# ZYNQ-JTAG.net
KiCad netlist of a schematic drawn in Altium Designer
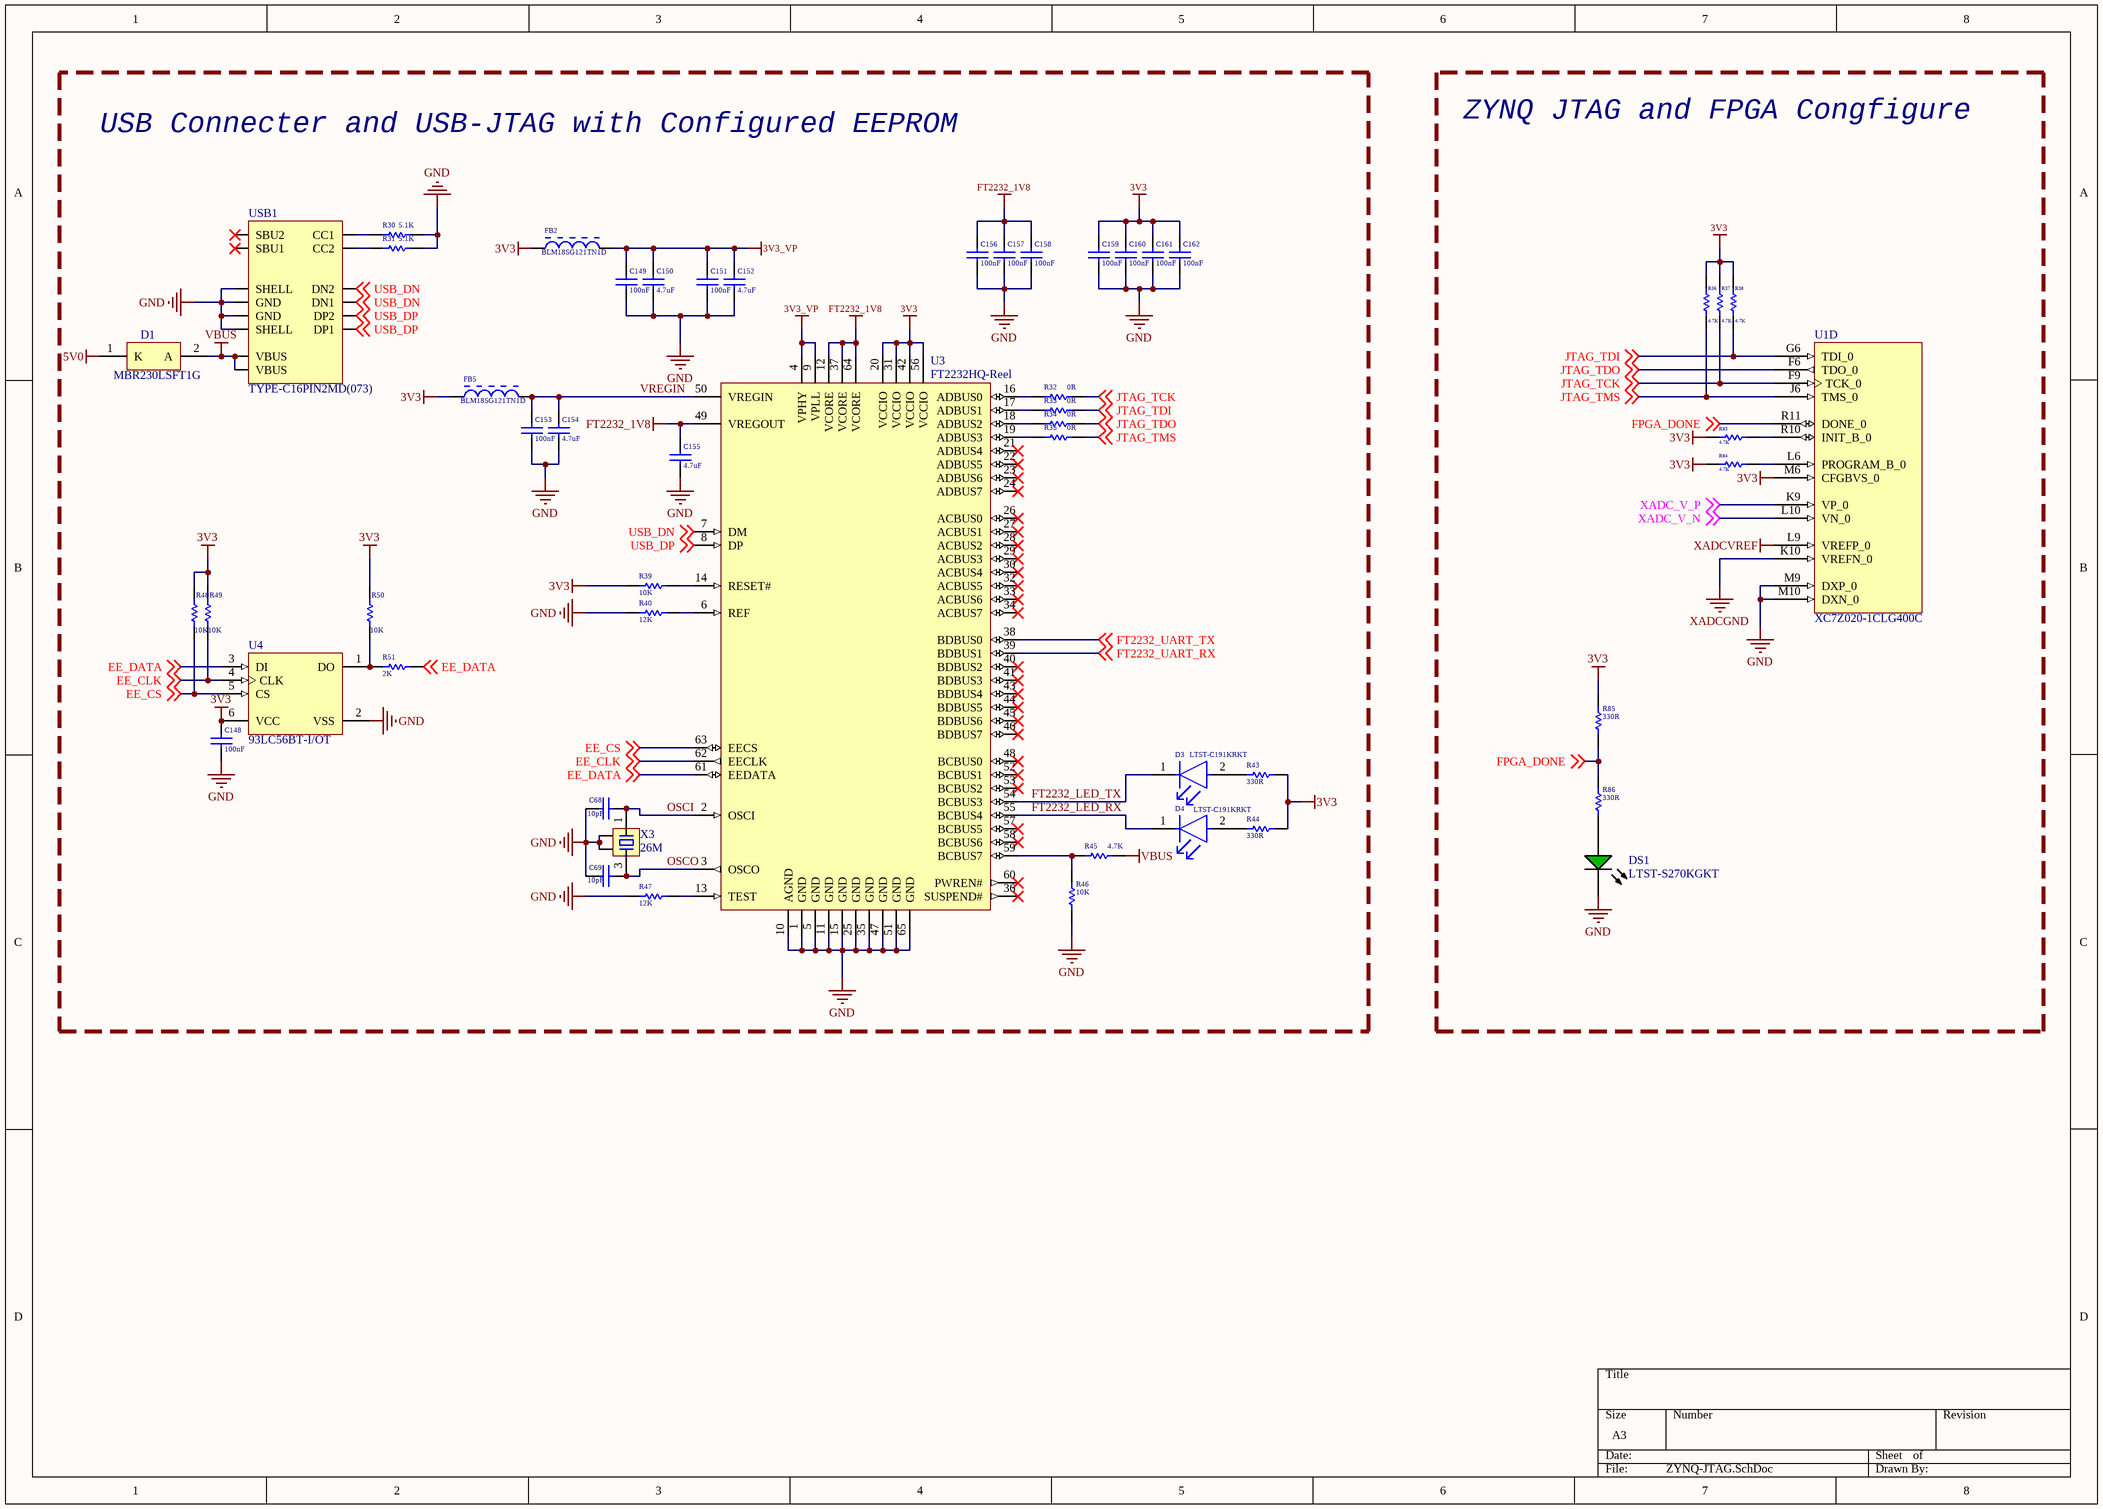
[diagram p0: ZYNQ-JTAG.SchDoc]

(export (version "E")
  (design (tool "Eeschema 10.0.6"))
  (components
    (comp (ref "C68")
      (value "10pF")
      (footprint "CAPC1005X55X25LL05T10")
      (fields (field (name "PART NUMBER") "GRM155R71H104KE14D") (field (name "MANUFACTURER") "Murata"))
      (libsource (lib "Altium Content Vault") (part "CAP"))
    )
    (comp (ref "C69")
      (value "10pF")
      (footprint "CAPC1005X55X25LL05T10")
      (fields (field (name "PART NUMBER") "GRM155R71H104KE14D") (field (name "MANUFACTURER") "Murata"))
      (libsource (lib "Altium Content Vault") (part "CAP"))
    )
    (comp (ref "C148")
      (value "100nF")
      (footprint "CAPC1005X55X25LL05T10")
      (fields (field (name "PART NUMBER") "GRM155R71H104KE14D") (field (name "MANUFACTURER") "Murata"))
      (libsource (lib "Altium Content Vault") (part "CAP"))
    )
    (comp (ref "C149")
      (value "100nF")
      (footprint "CAPC1005X55X25LL05T10")
      (fields (field (name "PART NUMBER") "GRM155R71H104KE14D") (field (name "MANUFACTURER") "Murata"))
      (libsource (lib "Altium Content Vault") (part "CAP"))
    )
    (comp (ref "C150")
      (value "4.7uF")
      (footprint "CAPC1005X55X25LL05T10")
      (fields (field (name "PART NUMBER") "GRM155R71H104KE14D") (field (name "MANUFACTURER") "Murata"))
      (libsource (lib "Altium Content Vault") (part "CAP"))
    )
    (comp (ref "C151")
      (value "100nF")
      (footprint "CAPC1005X55X25LL05T10")
      (fields (field (name "PART NUMBER") "GRM155R71H104KE14D") (field (name "MANUFACTURER") "Murata"))
      (libsource (lib "Altium Content Vault") (part "CAP"))
    )
    (comp (ref "C152")
      (value "4.7uF")
      (footprint "CAPC1005X55X25LL05T10")
      (fields (field (name "PART NUMBER") "GRM155R71H104KE14D") (field (name "MANUFACTURER") "Murata"))
      (libsource (lib "Altium Content Vault") (part "CAP"))
    )
    (comp (ref "C153")
      (value "100nF")
      (footprint "CAPC1005X55X25LL05T10")
      (fields (field (name "PART NUMBER") "GRM155R71H104KE14D") (field (name "MANUFACTURER") "Murata"))
      (libsource (lib "Altium Content Vault") (part "CAP"))
    )
    (comp (ref "C154")
      (value "4.7uF")
      (footprint "CAPC1005X55X25LL05T10")
      (fields (field (name "PART NUMBER") "GRM155R71H104KE14D") (field (name "MANUFACTURER") "Murata"))
      (libsource (lib "Altium Content Vault") (part "CAP"))
    )
    (comp (ref "C155")
      (value "4.7uF")
      (footprint "CAPC1005X55X25LL05T10")
      (fields (field (name "PART NUMBER") "GRM155R71H104KE14D") (field (name "MANUFACTURER") "Murata"))
      (libsource (lib "Altium Content Vault") (part "CAP"))
    )
    (comp (ref "C156")
      (value "100nF")
      (footprint "CAPC1005X55X25LL05T10")
      (fields (field (name "PART NUMBER") "GRM155R71H104KE14D") (field (name "MANUFACTURER") "Murata"))
      (libsource (lib "Altium Content Vault") (part "CAP"))
    )
    (comp (ref "C157")
      (value "100nF")
      (footprint "CAPC1005X55X25LL05T10")
      (fields (field (name "PART NUMBER") "GRM155R71H104KE14D") (field (name "MANUFACTURER") "Murata"))
      (libsource (lib "Altium Content Vault") (part "CAP"))
    )
    (comp (ref "C158")
      (value "100nF")
      (footprint "CAPC1005X55X25LL05T10")
      (fields (field (name "PART NUMBER") "GRM155R71H104KE14D") (field (name "MANUFACTURER") "Murata"))
      (libsource (lib "Altium Content Vault") (part "CAP"))
    )
    (comp (ref "C159")
      (value "100nF")
      (footprint "CAPC1005X55X25LL05T10")
      (fields (field (name "PART NUMBER") "GRM155R71H104KE14D") (field (name "MANUFACTURER") "Murata"))
      (libsource (lib "Altium Content Vault") (part "CAP"))
    )
    (comp (ref "C160")
      (value "100nF")
      (footprint "CAPC1005X55X25LL05T10")
      (fields (field (name "PART NUMBER") "GRM155R71H104KE14D") (field (name "MANUFACTURER") "Murata"))
      (libsource (lib "Altium Content Vault") (part "CAP"))
    )
    (comp (ref "C161")
      (value "100nF")
      (footprint "CAPC1005X55X25LL05T10")
      (fields (field (name "PART NUMBER") "GRM155R71H104KE14D") (field (name "MANUFACTURER") "Murata"))
      (libsource (lib "Altium Content Vault") (part "CAP"))
    )
    (comp (ref "C162")
      (value "100nF")
      (footprint "CAPC1005X55X25LL05T10")
      (fields (field (name "PART NUMBER") "GRM155R71H104KE14D") (field (name "MANUFACTURER") "Murata"))
      (libsource (lib "Altium Content Vault") (part "CAP"))
    )
    (comp (ref "D1")
      (value "MBR230LSFT1G")
      (footprint "ONSC-SOD-123FL-2-498-01_V")
      (description "Schottky Power Rectifier, 2-Pin SOD-123, Pb-Free, Tape and Reel")
      (fields (field (name "MANUFACTURER") "On Semiconductor"))
      (libsource (lib "Altium Content Vault") (part "ONSC-D-K1A2-2_A"))
    )
    (comp (ref "D3")
      (value "LTST-C191KRKT")
      (footprint "FP-LTST-C191KRKT-MFG")
      (libsource (lib "Altium Content Vault") (part "8706943c75ba83719d021d2fdc84c58"))
    )
    (comp (ref "D4")
      (value "LTST-C191KRKT")
      (footprint "FP-LTST-C191KRKT-MFG")
      (libsource (lib "Altium Content Vault") (part "8706943c75ba83719d021d2fdc84c58"))
    )
    (comp (ref "DS1")
      (value "LTST-S270KGKT")
      (footprint "LTST-LTST-S270KGKT-2_V")
      (description "Ultra Bright AlInGaP Chip LED, 75 mW, -30 to 85 degC, 2-Pin SMD (0604), RoHS, Tape and Reel")
      (fields (field (name "MANUFACTURER") "Lite-On"))
      (libsource (lib "Altium Content Vault") (part "LED-GREEN-KA-2"))
    )
    (comp (ref "FB2")
      (value "BLM18SG121TN1D")
      (footprint "MURA-BLM18SG-B40-CHIP-2_V6")
      (fields (field (name "MANUFACTURER") "Murata"))
      (libsource (lib "Altium Content Vault") (part "MURA-FB-2"))
    )
    (comp (ref "FB5")
      (value "BLM18SG121TN1D")
      (footprint "MURA-BLM18SG-B40-CHIP-2_V6")
      (fields (field (name "MANUFACTURER") "Murata"))
      (libsource (lib "Altium Content Vault") (part "MURA-FB-2"))
    )
    (comp (ref "R30")
      (value "5.1K")
      (footprint "RESC1005X40X25LL05T05")
      (fields (field (name "MANUFACTURER") "Panasonic") (field (name "PART NUMBER") "ERJ-2RKF40R2X"))
      (libsource (lib "Altium Content Vault") (part "RES"))
    )
    (comp (ref "R31")
      (value "5.1K")
      (footprint "RESC1005X40X25LL05T05")
      (fields (field (name "MANUFACTURER") "Panasonic") (field (name "PART NUMBER") "ERJ-2RKF40R2X"))
      (libsource (lib "Altium Content Vault") (part "RES"))
    )
    (comp (ref "R32")
      (value "0R")
      (footprint "RESC1005X40X25LL05T05")
      (fields (field (name "MANUFACTURER") "Panasonic") (field (name "PART NUMBER") "ERJ-2RKF40R2X"))
      (libsource (lib "Altium Content Vault") (part "RES"))
    )
    (comp (ref "R33")
      (value "0R")
      (footprint "RESC1005X40X25LL05T05")
      (fields (field (name "MANUFACTURER") "Panasonic") (field (name "PART NUMBER") "ERJ-2RKF40R2X"))
      (libsource (lib "Altium Content Vault") (part "RES"))
    )
    (comp (ref "R34")
      (value "0R")
      (footprint "RESC1005X40X25LL05T05")
      (fields (field (name "MANUFACTURER") "Panasonic") (field (name "PART NUMBER") "ERJ-2RKF40R2X"))
      (libsource (lib "Altium Content Vault") (part "RES"))
    )
    (comp (ref "R35")
      (value "0R")
      (footprint "RESC1005X40X25LL05T05")
      (fields (field (name "MANUFACTURER") "Panasonic") (field (name "PART NUMBER") "ERJ-2RKF40R2X"))
      (libsource (lib "Altium Content Vault") (part "RES"))
    )
    (comp (ref "R36")
      (value "4.7K")
      (footprint "RESC1005X40X25LL05T05")
      (fields (field (name "MANUFACTURER") "Panasonic") (field (name "PART NUMBER") "ERJ-2RKF40R2X"))
      (libsource (lib "Altium Content Vault") (part "RES"))
    )
    (comp (ref "R37")
      (value "4.7K")
      (footprint "RESC1005X40X25LL05T05")
      (fields (field (name "MANUFACTURER") "Panasonic") (field (name "PART NUMBER") "ERJ-2RKF40R2X"))
      (libsource (lib "Altium Content Vault") (part "RES"))
    )
    (comp (ref "R38")
      (value "4.7K")
      (footprint "RESC1005X40X25LL05T05")
      (fields (field (name "MANUFACTURER") "Panasonic") (field (name "PART NUMBER") "ERJ-2RKF40R2X"))
      (libsource (lib "Altium Content Vault") (part "RES"))
    )
    (comp (ref "R39")
      (value "10K")
      (footprint "RESC1005X40X25LL05T05")
      (fields (field (name "MANUFACTURER") "Panasonic") (field (name "PART NUMBER") "ERJ-2RKF40R2X"))
      (libsource (lib "Altium Content Vault") (part "RES"))
    )
    (comp (ref "R40")
      (value "12K")
      (footprint "RESC1005X40X25LL05T05")
      (fields (field (name "MANUFACTURER") "Panasonic") (field (name "PART NUMBER") "ERJ-2RKF40R2X"))
      (libsource (lib "Altium Content Vault") (part "RES"))
    )
    (comp (ref "R43")
      (value "330R")
      (footprint "RESC1005X40X25LL05T05")
      (fields (field (name "MANUFACTURER") "Panasonic") (field (name "PART NUMBER") "ERJ-2RKF40R2X"))
      (libsource (lib "Altium Content Vault") (part "RES"))
    )
    (comp (ref "R44")
      (value "330R")
      (footprint "RESC1005X40X25LL05T05")
      (fields (field (name "MANUFACTURER") "Panasonic") (field (name "PART NUMBER") "ERJ-2RKF40R2X"))
      (libsource (lib "Altium Content Vault") (part "RES"))
    )
    (comp (ref "R45")
      (value "4.7K")
      (footprint "RESC1005X40X25LL05T05")
      (fields (field (name "MANUFACTURER") "Panasonic") (field (name "PART NUMBER") "ERJ-2RKF40R2X"))
      (libsource (lib "Altium Content Vault") (part "RES"))
    )
    (comp (ref "R46")
      (value "10K")
      (footprint "RESC1005X40X25LL05T05")
      (fields (field (name "MANUFACTURER") "Panasonic") (field (name "PART NUMBER") "ERJ-2RKF40R2X"))
      (libsource (lib "Altium Content Vault") (part "RES"))
    )
    (comp (ref "R47")
      (value "12K")
      (footprint "RESC1005X40X25LL05T05")
      (fields (field (name "MANUFACTURER") "Panasonic") (field (name "PART NUMBER") "ERJ-2RKF40R2X"))
      (libsource (lib "Altium Content Vault") (part "RES"))
    )
    (comp (ref "R48")
      (value "10K")
      (footprint "RESC1005X40X25LL05T05")
      (fields (field (name "MANUFACTURER") "Panasonic") (field (name "PART NUMBER") "ERJ-2RKF40R2X"))
      (libsource (lib "Altium Content Vault") (part "RES"))
    )
    (comp (ref "R49")
      (value "10K")
      (footprint "RESC1005X40X25LL05T05")
      (fields (field (name "MANUFACTURER") "Panasonic") (field (name "PART NUMBER") "ERJ-2RKF40R2X"))
      (libsource (lib "Altium Content Vault") (part "RES"))
    )
    (comp (ref "R50")
      (value "10K")
      (footprint "RESC1005X40X25LL05T05")
      (fields (field (name "MANUFACTURER") "Panasonic") (field (name "PART NUMBER") "ERJ-2RKF40R2X"))
      (libsource (lib "Altium Content Vault") (part "RES"))
    )
    (comp (ref "R51")
      (value "2K")
      (footprint "RESC1005X40X25LL05T05")
      (fields (field (name "MANUFACTURER") "Panasonic") (field (name "PART NUMBER") "ERJ-2RKF40R2X"))
      (libsource (lib "Altium Content Vault") (part "RES"))
    )
    (comp (ref "R83")
      (value "4.7K")
      (footprint "RESC1005X40X25LL05T05")
      (fields (field (name "MANUFACTURER") "Panasonic") (field (name "PART NUMBER") "ERJ-2RKF40R2X"))
      (libsource (lib "Altium Content Vault") (part "RES"))
    )
    (comp (ref "R84")
      (value "4.7K")
      (footprint "RESC1005X40X25LL05T05")
      (fields (field (name "MANUFACTURER") "Panasonic") (field (name "PART NUMBER") "ERJ-2RKF40R2X"))
      (libsource (lib "Altium Content Vault") (part "RES"))
    )
    (comp (ref "R85")
      (value "330R")
      (footprint "RESC1005X40X25LL05T05")
      (fields (field (name "MANUFACTURER") "Panasonic") (field (name "PART NUMBER") "ERJ-2RKF40R2X"))
      (libsource (lib "Altium Content Vault") (part "RES"))
    )
    (comp (ref "R86")
      (value "330R")
      (footprint "RESC1005X40X25LL05T05")
      (fields (field (name "MANUFACTURER") "Panasonic") (field (name "PART NUMBER") "ERJ-2RKF40R2X"))
      (libsource (lib "Altium Content Vault") (part "RES"))
    )
    (comp (ref "U1")
      (value "XC7Z020-1CLG400C")
      (footprint "CLG400")
      (fields (field (name "GENERIC PART NUMBER") "XC7Z020"))
      (libsource (lib "Altium Content Vault") (part "XNLX-XC7Z020-CLG400"))
    )
    (comp (ref "U3")
      (value "FT2232HQ-Reel")
      (footprint "QFN64_2_L")
      (description "Dual High Speed USB To Multipurpose UART/FIFO IC, 64-pin QFN, Tape and Reel")
      (fields (field (name "MANUFACTURER") "FTDI"))
      (libsource (lib "Altium Content Vault") (part "COM-UART-FT2232H-QFN64"))
    )
    (comp (ref "U4")
      (value "93LC56BT-I/OT")
      (footprint "SOT-23-OT6_N")
      (description "2K, 128x16-bit, 2.5V Microwire Serial EEPROM, 6-Pin SOT-23, Industrial Temperature, Tape and Reel")
      (libsource (lib "Altium Content Vault") (part "MEM-SEEPROM-93AA46B-OT-6"))
    )
    (comp (ref "USB1")
      (value "TYPE-C16PIN2MD(073)")
      (footprint "TYPE-C16PIN2MD(073)-Footprint")
      (description "Type-C 母 卧贴 带定位柱 不锈钢外壳 2次模顶")
      (libsource (lib "HainanU-RoboMaster-硬件组") (part "TypeC-16P"))
    )
    (comp (ref "X3")
      (value "26M")
      (footprint "XTAL-3225-4P")
      (description "4脚无源晶振(谐振器）")
      (libsource (lib "0.1 - 电阻-电容-电感-保险丝-晶振-晶体-磁珠-电位器-法拉电容-馈通电容") (part "XTAL-4P"))
    )
  )
  (nets
    (net (code "1") (name "/FT2232_LED_RX") (class "Default")
      (node (ref "D4") (pin "1") (pinfunction "C_1") (pintype "passive"))
      (node (ref "U3") (pin "55") (pinfunction "BCBUS4_55") (pintype "bidirectional"))
    )
    (net (code "2") (name "/FT2232_LED_TX") (class "Default")
      (node (ref "D3") (pin "1") (pinfunction "C_1") (pintype "passive"))
      (node (ref "U3") (pin "54") (pinfunction "BCBUS3_54") (pintype "bidirectional"))
    )
    (net (code "3") (name "/OSCI") (class "Default")
      (node (ref "C68") (pin "1") (pinfunction "1_1") (pintype "passive"))
      (node (ref "U3") (pin "2") (pinfunction "OSCI_2") (pintype "input"))
      (node (ref "X3") (pin "1") (pinfunction "1_1") (pintype "passive"))
    )
    (net (code "4") (name "/OSCO") (class "Default")
      (node (ref "C69") (pin "1") (pinfunction "1_1") (pintype "passive"))
      (node (ref "U3") (pin "3") (pinfunction "OSCO_3") (pintype "output"))
      (node (ref "X3") (pin "3") (pinfunction "3_3") (pintype "passive"))
    )
    (net (code "5") (name "/VREGIN") (class "Default")
      (node (ref "C153") (pin "1") (pinfunction "1_1") (pintype "passive"))
      (node (ref "C154") (pin "1") (pinfunction "1_1") (pintype "passive"))
      (node (ref "FB5") (pin "2") (pinfunction "2_2") (pintype "passive"))
      (node (ref "U3") (pin "50") (pinfunction "VREGIN_50") (pintype "power_in"))
    )
    (net (code "6") (name "3V3") (class "Default")
      (node (ref "C148") (pin "1") (pinfunction "1_1") (pintype "passive"))
      (node (ref "C159") (pin "1") (pinfunction "1_1") (pintype "passive"))
      (node (ref "C160") (pin "1") (pinfunction "1_1") (pintype "passive"))
      (node (ref "C161") (pin "1") (pinfunction "1_1") (pintype "passive"))
      (node (ref "C162") (pin "1") (pinfunction "1_1") (pintype "passive"))
      (node (ref "FB2") (pin "1") (pinfunction "1_1") (pintype "passive"))
      (node (ref "FB5") (pin "1") (pinfunction "1_1") (pintype "passive"))
      (node (ref "R36") (pin "1") (pinfunction "1_1") (pintype "passive"))
      (node (ref "R37") (pin "1") (pinfunction "1_1") (pintype "passive"))
      (node (ref "R38") (pin "1") (pinfunction "1_1") (pintype "passive"))
      (node (ref "R39") (pin "2") (pinfunction "2_2") (pintype "passive"))
      (node (ref "R43") (pin "1") (pinfunction "1_1") (pintype "passive"))
      (node (ref "R44") (pin "1") (pinfunction "1_1") (pintype "passive"))
      (node (ref "R48") (pin "2") (pinfunction "2_2") (pintype "passive"))
      (node (ref "R49") (pin "2") (pinfunction "2_2") (pintype "passive"))
      (node (ref "R50") (pin "2") (pinfunction "2_2") (pintype "passive"))
      (node (ref "R83") (pin "1") (pinfunction "1_1") (pintype "passive"))
      (node (ref "R84") (pin "1") (pinfunction "1_1") (pintype "passive"))
      (node (ref "R85") (pin "2") (pinfunction "2_2") (pintype "passive"))
      (node (ref "U1") (pin "M6") (pinfunction "CFGBVS_0_M6") (pintype "input"))
      (node (ref "U3") (pin "20") (pinfunction "VCCIO_20") (pintype "power_in"))
      (node (ref "U3") (pin "31") (pinfunction "VCCIO_31") (pintype "power_in"))
      (node (ref "U3") (pin "42") (pinfunction "VCCIO_42") (pintype "power_in"))
      (node (ref "U3") (pin "56") (pinfunction "VCCIO_56") (pintype "power_in"))
      (node (ref "U4") (pin "6") (pinfunction "VCC_6") (pintype "power_in"))
    )
    (net (code "7") (name "3V3_VP") (class "Default")
      (node (ref "C149") (pin "1") (pinfunction "1_1") (pintype "passive"))
      (node (ref "C150") (pin "1") (pinfunction "1_1") (pintype "passive"))
      (node (ref "C151") (pin "1") (pinfunction "1_1") (pintype "passive"))
      (node (ref "C152") (pin "1") (pinfunction "1_1") (pintype "passive"))
      (node (ref "FB2") (pin "2") (pinfunction "2_2") (pintype "passive"))
      (node (ref "U3") (pin "4") (pinfunction "VPHY_4") (pintype "power_in"))
      (node (ref "U3") (pin "9") (pinfunction "VPLL_9") (pintype "power_in"))
    )
    (net (code "8") (name "5V0") (class "Default")
      (node (ref "D1") (pin "1") (pinfunction "K_1") (pintype "passive"))
    )
    (net (code "9") (name "EE_CLK") (class "Default")
      (node (ref "R49") (pin "1") (pinfunction "1_1") (pintype "passive"))
      (node (ref "U3") (pin "62") (pinfunction "EECLK_62") (pintype "output"))
      (node (ref "U4") (pin "4") (pinfunction "CLK_4") (pintype "input"))
    )
    (net (code "10") (name "EE_CS") (class "Default")
      (node (ref "R48") (pin "1") (pinfunction "1_1") (pintype "passive"))
      (node (ref "U3") (pin "63") (pinfunction "EECS_63") (pintype "bidirectional"))
      (node (ref "U4") (pin "5") (pinfunction "CS_5") (pintype "input"))
    )
    (net (code "11") (name "EE_DATA") (class "Default")
      (node (ref "R51") (pin "1") (pinfunction "1_1") (pintype "passive"))
      (node (ref "U3") (pin "61") (pinfunction "EEDATA_61") (pintype "bidirectional"))
      (node (ref "U4") (pin "3") (pinfunction "DI_3") (pintype "input"))
    )
    (net (code "12") (name "FPGA_DONE") (class "Default")
      (node (ref "R85") (pin "1") (pinfunction "1_1") (pintype "passive"))
      (node (ref "R86") (pin "2") (pinfunction "2_2") (pintype "passive"))
      (node (ref "U1") (pin "R11") (pinfunction "DONE_0_R11") (pintype "bidirectional"))
    )
    (net (code "13") (name "FT2232_1V8") (class "Default")
      (node (ref "C155") (pin "1") (pinfunction "1_1") (pintype "passive"))
      (node (ref "C156") (pin "1") (pinfunction "1_1") (pintype "passive"))
      (node (ref "C157") (pin "1") (pinfunction "1_1") (pintype "passive"))
      (node (ref "C158") (pin "1") (pinfunction "1_1") (pintype "passive"))
      (node (ref "U3") (pin "12") (pinfunction "VCORE_12") (pintype "power_in"))
      (node (ref "U3") (pin "37") (pinfunction "VCORE_37") (pintype "power_in"))
      (node (ref "U3") (pin "49") (pinfunction "VREGOUT_49") (pintype "power_in"))
      (node (ref "U3") (pin "64") (pinfunction "VCORE_64") (pintype "power_in"))
    )
    (net (code "14") (name "FT2232_UART_RX") (class "Default")
      (node (ref "U3") (pin "39") (pinfunction "BDBUS1_39") (pintype "bidirectional"))
    )
    (net (code "15") (name "FT2232_UART_TX") (class "Default")
      (node (ref "U3") (pin "38") (pinfunction "BDBUS0_38") (pintype "bidirectional"))
    )
    (net (code "16") (name "GND") (class "Default")
      (node (ref "C148") (pin "2") (pinfunction "2_2") (pintype "passive"))
      (node (ref "C149") (pin "2") (pinfunction "2_2") (pintype "passive"))
      (node (ref "C150") (pin "2") (pinfunction "2_2") (pintype "passive"))
      (node (ref "C151") (pin "2") (pinfunction "2_2") (pintype "passive"))
      (node (ref "C152") (pin "2") (pinfunction "2_2") (pintype "passive"))
      (node (ref "C153") (pin "2") (pinfunction "2_2") (pintype "passive"))
      (node (ref "C154") (pin "2") (pinfunction "2_2") (pintype "passive"))
      (node (ref "C155") (pin "2") (pinfunction "2_2") (pintype "passive"))
      (node (ref "C156") (pin "2") (pinfunction "2_2") (pintype "passive"))
      (node (ref "C157") (pin "2") (pinfunction "2_2") (pintype "passive"))
      (node (ref "C158") (pin "2") (pinfunction "2_2") (pintype "passive"))
      (node (ref "C159") (pin "2") (pinfunction "2_2") (pintype "passive"))
      (node (ref "C160") (pin "2") (pinfunction "2_2") (pintype "passive"))
      (node (ref "C161") (pin "2") (pinfunction "2_2") (pintype "passive"))
      (node (ref "C162") (pin "2") (pinfunction "2_2") (pintype "passive"))
      (node (ref "C68") (pin "2") (pinfunction "2_2") (pintype "passive"))
      (node (ref "C69") (pin "2") (pinfunction "2_2") (pintype "passive"))
      (node (ref "DS1") (pin "1") (pinfunction "K_1") (pintype "passive"))
      (node (ref "R30") (pin "1") (pinfunction "1_1") (pintype "passive"))
      (node (ref "R31") (pin "1") (pinfunction "1_1") (pintype "passive"))
      (node (ref "R40") (pin "1") (pinfunction "1_1") (pintype "passive"))
      (node (ref "R46") (pin "1") (pinfunction "1_1") (pintype "passive"))
      (node (ref "R47") (pin "1") (pinfunction "1_1") (pintype "passive"))
      (node (ref "U1") (pin "M10") (pinfunction "DXN_0_M10") (pintype "input"))
      (node (ref "U1") (pin "M9") (pinfunction "DXP_0_M9") (pintype "input"))
      (node (ref "U3") (pin "1") (pinfunction "GND_1") (pintype "power_in"))
      (node (ref "U3") (pin "10") (pinfunction "AGND_10") (pintype "power_in"))
      (node (ref "U3") (pin "11") (pinfunction "GND_11") (pintype "power_in"))
      (node (ref "U3") (pin "15") (pinfunction "GND_15") (pintype "power_in"))
      (node (ref "U3") (pin "25") (pinfunction "GND_25") (pintype "power_in"))
      (node (ref "U3") (pin "35") (pinfunction "GND_35") (pintype "power_in"))
      (node (ref "U3") (pin "47") (pinfunction "GND_47") (pintype "power_in"))
      (node (ref "U3") (pin "5") (pinfunction "GND_5") (pintype "power_in"))
      (node (ref "U3") (pin "51") (pinfunction "GND_51") (pintype "power_in"))
      (node (ref "U3") (pin "65") (pinfunction "GND_65") (pintype "power_in"))
      (node (ref "U4") (pin "2") (pinfunction "VSS_2") (pintype "power_in"))
      (node (ref "USB1") (pin "1") (pinfunction "GND_1") (pintype "passive"))
      (node (ref "USB1") (pin "12") (pinfunction "GND_12") (pintype "passive"))
      (node (ref "USB1") (pin "13") (pinfunction "SHELL_13") (pintype "passive"))
      (node (ref "USB1") (pin "14") (pinfunction "SHELL_14") (pintype "passive"))
      (node (ref "X3") (pin "2") (pinfunction "2_2") (pintype "passive"))
      (node (ref "X3") (pin "4") (pinfunction "4_4") (pintype "passive"))
    )
    (net (code "17") (name "JTAG_TCK") (class "Default")
      (node (ref "R32") (pin "2") (pinfunction "2_2") (pintype "passive"))
      (node (ref "R37") (pin "2") (pinfunction "2_2") (pintype "passive"))
      (node (ref "U1") (pin "F9") (pinfunction "TCK_0_F9") (pintype "input"))
    )
    (net (code "18") (name "JTAG_TDI") (class "Default")
      (node (ref "R33") (pin "2") (pinfunction "2_2") (pintype "passive"))
      (node (ref "R38") (pin "2") (pinfunction "2_2") (pintype "passive"))
      (node (ref "U1") (pin "G6") (pinfunction "TDI_0_G6") (pintype "input"))
    )
    (net (code "19") (name "JTAG_TDO") (class "Default")
      (node (ref "R34") (pin "2") (pinfunction "2_2") (pintype "passive"))
      (node (ref "U1") (pin "F6") (pinfunction "TDO_0_F6") (pintype "output"))
    )
    (net (code "20") (name "JTAG_TMS") (class "Default")
      (node (ref "R35") (pin "2") (pinfunction "2_2") (pintype "passive"))
      (node (ref "R36") (pin "2") (pinfunction "2_2") (pintype "passive"))
      (node (ref "U1") (pin "J6") (pinfunction "TMS_0_J6") (pintype "input"))
    )
    (net (code "21") (name "Net-(D3-A)") (class "Default")
      (node (ref "D3") (pin "2") (pinfunction "A_2") (pintype "passive"))
      (node (ref "R43") (pin "2") (pinfunction "2_2") (pintype "passive"))
    )
    (net (code "22") (name "Net-(D4-A)") (class "Default")
      (node (ref "D4") (pin "2") (pinfunction "A_2") (pintype "passive"))
      (node (ref "R44") (pin "2") (pinfunction "2_2") (pintype "passive"))
    )
    (net (code "23") (name "Net-(DS1-A)") (class "Default")
      (node (ref "DS1") (pin "2") (pinfunction "A_2") (pintype "passive"))
      (node (ref "R86") (pin "1") (pinfunction "1_1") (pintype "passive"))
    )
    (net (code "24") (name "Net-(U1D-INIT_B_0)") (class "Default")
      (node (ref "R83") (pin "2") (pinfunction "2_2") (pintype "passive"))
      (node (ref "U1") (pin "R10") (pinfunction "INIT_B_0_R10") (pintype "bidirectional"))
    )
    (net (code "25") (name "Net-(U1D-PROGRAM_B_0)") (class "Default")
      (node (ref "R84") (pin "2") (pinfunction "2_2") (pintype "passive"))
      (node (ref "U1") (pin "L6") (pinfunction "PROGRAM_B_0_L6") (pintype "input"))
    )
    (net (code "26") (name "Net-(U3-ADBUS0)") (class "Default")
      (node (ref "R32") (pin "1") (pinfunction "1_1") (pintype "passive"))
      (node (ref "U3") (pin "16") (pinfunction "ADBUS0_16") (pintype "bidirectional"))
    )
    (net (code "27") (name "Net-(U3-ADBUS1)") (class "Default")
      (node (ref "R33") (pin "1") (pinfunction "1_1") (pintype "passive"))
      (node (ref "U3") (pin "17") (pinfunction "ADBUS1_17") (pintype "bidirectional"))
    )
    (net (code "28") (name "Net-(U3-ADBUS2)") (class "Default")
      (node (ref "R34") (pin "1") (pinfunction "1_1") (pintype "passive"))
      (node (ref "U3") (pin "18") (pinfunction "ADBUS2_18") (pintype "bidirectional"))
    )
    (net (code "29") (name "Net-(U3-ADBUS3)") (class "Default")
      (node (ref "R35") (pin "1") (pinfunction "1_1") (pintype "passive"))
      (node (ref "U3") (pin "19") (pinfunction "ADBUS3_19") (pintype "bidirectional"))
    )
    (net (code "30") (name "Net-(U3-BCBUS7)") (class "Default")
      (node (ref "R45") (pin "1") (pinfunction "1_1") (pintype "passive"))
      (node (ref "R46") (pin "2") (pinfunction "2_2") (pintype "passive"))
      (node (ref "U3") (pin "59") (pinfunction "BCBUS7_59") (pintype "bidirectional"))
    )
    (net (code "31") (name "Net-(U3-REF)") (class "Default")
      (node (ref "R40") (pin "2") (pinfunction "2_2") (pintype "passive"))
      (node (ref "U3") (pin "6") (pinfunction "REF_6") (pintype "input"))
    )
    (net (code "32") (name "Net-(U3-RESET#)") (class "Default")
      (node (ref "R39") (pin "1") (pinfunction "1_1") (pintype "passive"))
      (node (ref "U3") (pin "14") (pinfunction "RESET#_14") (pintype "input"))
    )
    (net (code "33") (name "Net-(U3-TEST)") (class "Default")
      (node (ref "R47") (pin "2") (pinfunction "2_2") (pintype "passive"))
      (node (ref "U3") (pin "13") (pinfunction "TEST_13") (pintype "input"))
    )
    (net (code "34") (name "Net-(U4-DO)") (class "Default")
      (node (ref "R50") (pin "1") (pinfunction "1_1") (pintype "passive"))
      (node (ref "R51") (pin "2") (pinfunction "2_2") (pintype "passive"))
      (node (ref "U4") (pin "1") (pinfunction "DO_1") (pintype "tri_state"))
    )
    (net (code "35") (name "Net-(USB1-CC1)") (class "Default")
      (node (ref "R30") (pin "2") (pinfunction "2_2") (pintype "passive"))
      (node (ref "USB1") (pin "4") (pinfunction "CC1_4") (pintype "passive"))
    )
    (net (code "36") (name "Net-(USB1-CC2)") (class "Default")
      (node (ref "R31") (pin "2") (pinfunction "2_2") (pintype "passive"))
      (node (ref "USB1") (pin "10") (pinfunction "CC2_10") (pintype "passive"))
    )
    (net (code "37") (name "USB_DN") (class "Default")
      (node (ref "U3") (pin "7") (pinfunction "DM_7") (pintype "input"))
      (node (ref "USB1") (pin "5") (pinfunction "DN2_5") (pintype "passive"))
      (node (ref "USB1") (pin "7") (pinfunction "DN1_7") (pintype "passive"))
    )
    (net (code "38") (name "USB_DP") (class "Default")
      (node (ref "U3") (pin "8") (pinfunction "DP_8") (pintype "input"))
      (node (ref "USB1") (pin "6") (pinfunction "DP1_6") (pintype "passive"))
      (node (ref "USB1") (pin "8") (pinfunction "DP2_8") (pintype "passive"))
    )
    (net (code "39") (name "VBUS") (class "Default")
      (node (ref "D1") (pin "2") (pinfunction "A_2") (pintype "passive"))
      (node (ref "R45") (pin "2") (pinfunction "2_2") (pintype "passive"))
      (node (ref "USB1") (pin "11") (pinfunction "VBUS_11") (pintype "passive"))
      (node (ref "USB1") (pin "2") (pinfunction "VBUS_2") (pintype "passive"))
    )
    (net (code "40") (name "XADCGND") (class "Default")
      (node (ref "U1") (pin "K10") (pinfunction "VREFN_0_K10") (pintype "input"))
    )
    (net (code "41") (name "XADCVREF") (class "Default")
      (node (ref "U1") (pin "L9") (pinfunction "VREFP_0_L9") (pintype "input"))
    )
    (net (code "42") (name "XADC_V_N") (class "Default")
      (node (ref "U1") (pin "L10") (pinfunction "VN_0_L10") (pintype "input"))
    )
    (net (code "43") (name "XADC_V_P") (class "Default")
      (node (ref "U1") (pin "K9") (pinfunction "VP_0_K9") (pintype "input"))
    )
    (net (code "44") (name "unconnected-(U3-ACBUS0-Pad26)") (class "Default")
      (node (ref "U3") (pin "26") (pinfunction "ACBUS0_26") (pintype "bidirectional+no_connect"))
    )
    (net (code "45") (name "unconnected-(U3-ACBUS1-Pad27)") (class "Default")
      (node (ref "U3") (pin "27") (pinfunction "ACBUS1_27") (pintype "bidirectional+no_connect"))
    )
    (net (code "46") (name "unconnected-(U3-ACBUS2-Pad28)") (class "Default")
      (node (ref "U3") (pin "28") (pinfunction "ACBUS2_28") (pintype "bidirectional+no_connect"))
    )
    (net (code "47") (name "unconnected-(U3-ACBUS3-Pad29)") (class "Default")
      (node (ref "U3") (pin "29") (pinfunction "ACBUS3_29") (pintype "bidirectional+no_connect"))
    )
    (net (code "48") (name "unconnected-(U3-ACBUS4-Pad30)") (class "Default")
      (node (ref "U3") (pin "30") (pinfunction "ACBUS4_30") (pintype "bidirectional+no_connect"))
    )
    (net (code "49") (name "unconnected-(U3-ACBUS5-Pad32)") (class "Default")
      (node (ref "U3") (pin "32") (pinfunction "ACBUS5_32") (pintype "bidirectional+no_connect"))
    )
    (net (code "50") (name "unconnected-(U3-ACBUS6-Pad33)") (class "Default")
      (node (ref "U3") (pin "33") (pinfunction "ACBUS6_33") (pintype "bidirectional+no_connect"))
    )
    (net (code "51") (name "unconnected-(U3-ACBUS7-Pad34)") (class "Default")
      (node (ref "U3") (pin "34") (pinfunction "ACBUS7_34") (pintype "bidirectional+no_connect"))
    )
    (net (code "52") (name "unconnected-(U3-ADBUS4-Pad21)") (class "Default")
      (node (ref "U3") (pin "21") (pinfunction "ADBUS4_21") (pintype "bidirectional+no_connect"))
    )
    (net (code "53") (name "unconnected-(U3-ADBUS5-Pad22)") (class "Default")
      (node (ref "U3") (pin "22") (pinfunction "ADBUS5_22") (pintype "bidirectional+no_connect"))
    )
    (net (code "54") (name "unconnected-(U3-ADBUS6-Pad23)") (class "Default")
      (node (ref "U3") (pin "23") (pinfunction "ADBUS6_23") (pintype "bidirectional+no_connect"))
    )
    (net (code "55") (name "unconnected-(U3-ADBUS7-Pad24)") (class "Default")
      (node (ref "U3") (pin "24") (pinfunction "ADBUS7_24") (pintype "bidirectional+no_connect"))
    )
    (net (code "56") (name "unconnected-(U3-BCBUS0-Pad48)") (class "Default")
      (node (ref "U3") (pin "48") (pinfunction "BCBUS0_48") (pintype "bidirectional+no_connect"))
    )
    (net (code "57") (name "unconnected-(U3-BCBUS1-Pad52)") (class "Default")
      (node (ref "U3") (pin "52") (pinfunction "BCBUS1_52") (pintype "bidirectional+no_connect"))
    )
    (net (code "58") (name "unconnected-(U3-BCBUS2-Pad53)") (class "Default")
      (node (ref "U3") (pin "53") (pinfunction "BCBUS2_53") (pintype "bidirectional+no_connect"))
    )
    (net (code "59") (name "unconnected-(U3-BCBUS5-Pad57)") (class "Default")
      (node (ref "U3") (pin "57") (pinfunction "BCBUS5_57") (pintype "bidirectional+no_connect"))
    )
    (net (code "60") (name "unconnected-(U3-BCBUS6-Pad58)") (class "Default")
      (node (ref "U3") (pin "58") (pinfunction "BCBUS6_58") (pintype "bidirectional+no_connect"))
    )
    (net (code "61") (name "unconnected-(U3-BDBUS2-Pad40)") (class "Default")
      (node (ref "U3") (pin "40") (pinfunction "BDBUS2_40") (pintype "bidirectional+no_connect"))
    )
    (net (code "62") (name "unconnected-(U3-BDBUS3-Pad41)") (class "Default")
      (node (ref "U3") (pin "41") (pinfunction "BDBUS3_41") (pintype "bidirectional+no_connect"))
    )
    (net (code "63") (name "unconnected-(U3-BDBUS4-Pad43)") (class "Default")
      (node (ref "U3") (pin "43") (pinfunction "BDBUS4_43") (pintype "bidirectional+no_connect"))
    )
    (net (code "64") (name "unconnected-(U3-BDBUS5-Pad44)") (class "Default")
      (node (ref "U3") (pin "44") (pinfunction "BDBUS5_44") (pintype "bidirectional+no_connect"))
    )
    (net (code "65") (name "unconnected-(U3-BDBUS6-Pad45)") (class "Default")
      (node (ref "U3") (pin "45") (pinfunction "BDBUS6_45") (pintype "bidirectional+no_connect"))
    )
    (net (code "66") (name "unconnected-(U3-BDBUS7-Pad46)") (class "Default")
      (node (ref "U3") (pin "46") (pinfunction "BDBUS7_46") (pintype "bidirectional+no_connect"))
    )
    (net (code "67") (name "unconnected-(U3-PWREN#-Pad60)") (class "Default")
      (node (ref "U3") (pin "60") (pinfunction "PWREN#_60") (pintype "output+no_connect"))
    )
    (net (code "68") (name "unconnected-(U3-SUSPEND#-Pad36)") (class "Default")
      (node (ref "U3") (pin "36") (pinfunction "SUSPEND#_36") (pintype "output+no_connect"))
    )
    (net (code "69") (name "unconnected-(USB1-SBU1-Pad9)") (class "Default")
      (node (ref "USB1") (pin "9") (pinfunction "SBU1_9") (pintype "passive+no_connect"))
    )
    (net (code "70") (name "unconnected-(USB1-SBU2-Pad3)") (class "Default")
      (node (ref "USB1") (pin "3") (pinfunction "SBU2_3") (pintype "passive+no_connect"))
    )
  )
)
